# PeripheralMain.net
KiCad netlist of a schematic drawn in Altium Designer
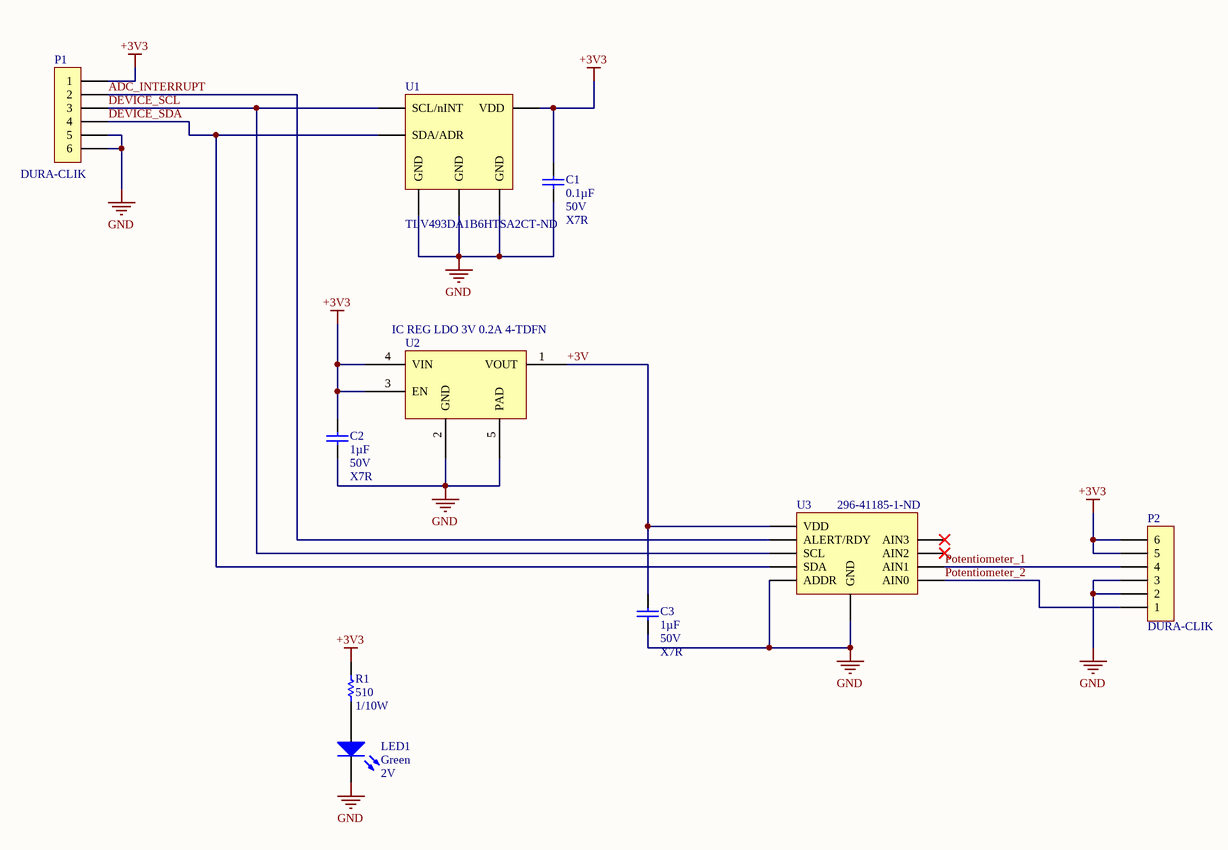
[diagram p0: PeripheralMain.SchDoc]

(export (version "E")
  (design (tool "Eeschema 10.0.6"))
  (components
    (comp (ref "C1")
      (value "CAP CER 0.1UF 50V 10% X7R 0603")
      (footprint "CAP, 0603")
      (description "0.10µF ±10% 50V Ceramic Capacitor X7R 0603 (1608 Metric)")
      (fields
        (field (name "TOLERANCE") "±10%")
        (field (name "CAPACITANCE") "0.1µF")
        (field (name "VOLTAGE") "50V")
        (field (name "TEMPERATURE COEFFICIENT") "X7R")
      )
      (libsource (lib "Schematic Diagrams") (part "CAP CER 0.1UF 50V 10% X7R 0603"))
    )
    (comp (ref "C2")
      (value "CAP CER 1UF 50V 10% X7R 0603")
      (footprint "CAP, 0603")
      (description "1µF ±10% 50V Ceramic Capacitor X7R 0603 (1608 Metric)")
      (fields
        (field (name "TOLERANCE") "±10%")
        (field (name "CAPACITANCE") "1µF")
        (field (name "VOLTAGE") "50V")
        (field (name "TEMPERATURE COEFFICIENT") "X7R")
      )
      (libsource (lib "Schematic Diagrams") (part "CAP CER 1UF 50V 10% X7R 0603"))
    )
    (comp (ref "C3")
      (value "CAP CER 1UF 50V 10% X7R 0603")
      (footprint "CAP, 0603")
      (description "1µF ±10% 50V Ceramic Capacitor X7R 0603 (1608 Metric)")
      (fields
        (field (name "TOLERANCE") "±10%")
        (field (name "CAPACITANCE") "1µF")
        (field (name "VOLTAGE") "50V")
        (field (name "TEMPERATURE COEFFICIENT") "X7R")
      )
      (libsource (lib "Schematic Diagrams") (part "CAP CER 1UF 50V 10% X7R 0603"))
    )
    (comp (ref "LED1")
      (value "LED GREEN CLEAR 2V 0603")
      (footprint "LED_0603")
      (description "Green 572nm LED Indication - Discrete 2V 0603 (1608 Metric)")
      (fields
        (field (name "MANUFACTURER") "Wurth Electronics Inc.")
        (field (name "MANUFACTURER PART NUMBER") "150060VS75000")
        (field (name "COLOR") "Green")
        (field (name "VOLTAGE - FORWARD (VF) (TYP)") "2V")
      )
      (libsource (lib "Schematic Diagrams") (part "LED GREEN CLEAR 2V 0603"))
    )
    (comp (ref "P1")
      (value "DURA-CLIK")
      (footprint "CONN, 6POS DURA-CLIK VERT")
      (description "6 Positions Header, Shrouded Connector 0.079\" (2.00mm) Surface Mount, Vertical Tin")
      (fields (field (name "MANUFACTURER") "Molex") (field (name "MANUFACTURER PART NUMBER") "5600200820"))
      (libsource (lib "") (part "CONN 6POS DURA-CLIK 0.079{dblquote}_1"))
    )
    (comp (ref "P2")
      (value "DURA-CLIK")
      (footprint "CONN, 6POS DURA-CLIK VERT")
      (description "6 Positions Header, Shrouded Connector 0.079\" (2.00mm) Surface Mount, Vertical Tin")
      (fields (field (name "MANUFACTURER") "Molex") (field (name "MANUFACTURER PART NUMBER") "5600200820"))
      (libsource (lib "Schematic Diagrams") (part "CONN 6POS DURA-CLIK 0.079{dblquote}"))
    )
    (comp (ref "R1")
      (value "RES 510 OHM 5% 1/10W 0603")
      (footprint "RES, 0603")
      (description "RES SMD 510 OHM 5% 1/10W 0603")
      (fields
        (field (name "TOLERANCE") "±5%")
        (field (name "RESISTANCE") "510")
        (field (name "POWER") "1/10W")
      )
      (libsource (lib "Schematic Diagrams") (part "RES 510 OHM 5% 1/10W 0603"))
    )
    (comp (ref "U1")
      (value "HALL EFFECT")
      (footprint "IC TLV496D MAG SENSOR TSOP-6")
      (description "Hall Effect Sensor Linear, Rotary Position External Magnet Not Included SMD (SMT) Tab")
      (fields
        (field (name "MANUFACTURER") "Infineon Technologies")
        (field (name "MANUFACTURER PART NUMBER") "TLV493DA1B6HTSA2")
        (field (name "SUPPLIER PART NUMBER 1") "TLV493DA1B6HTSA2CT-ND")
      )
      (libsource (lib "Schematic Diagrams") (part "IC SENSOR HALL I2C TSOP-6"))
    )
    (comp (ref "U2")
      (value "IC REG LDO 3V 0.2A 4-TDFN")
      (footprint "IC REG LDO 3V 0.2A 4-TDFN")
      (fields
        (field (name "MANUFACTURER") "Microchip Technology")
        (field (name "MANUFACTURER PART NUMBER") "MIC94310-PYMT-TR")
      )
      (libsource (lib "Schematic Diagrams") (part "IC REG LDO 3V 0.2A 4-TDFN"))
    )
    (comp (ref "U3")
      (value "Quad ADC")
      (footprint "IC ADC VSSOP10")
      (description "12 Bit Analog to Digital Converter 4 Input 1 Sigma-Delta 10-VSSOP")
      (fields
        (field (name "MANUFACTURER") "Texas Instruments")
        (field (name "MANUFACTURER PART NUMBER") "ADS1015IDGSR")
        (field (name "SUPPLIER PART NUMBER 1") "296-41185-1-ND")
      )
      (libsource (lib "Schematic Diagrams") (part "IC ADC 12-BIT VSSOP-10"))
    )
  )
  (nets
    (net (code "1") (name "+3V3") (class "Default")
      (node (ref "C1") (pin "1") (pinfunction "1_1") (pintype "passive"))
      (node (ref "C2") (pin "1") (pinfunction "1_1") (pintype "passive"))
      (node (ref "P1") (pin "1") (pinfunction "1_1") (pintype "passive"))
      (node (ref "P2") (pin "5") (pinfunction "5_5") (pintype "passive"))
      (node (ref "P2") (pin "6") (pinfunction "6_6") (pintype "passive"))
      (node (ref "R1") (pin "1") (pinfunction "1_1") (pintype "passive"))
      (node (ref "U1") (pin "4") (pinfunction "VDD_4") (pintype "passive"))
      (node (ref "U2") (pin "3") (pinfunction "EN_3") (pintype "passive"))
      (node (ref "U2") (pin "4") (pinfunction "VIN_4") (pintype "passive"))
    )
    (net (code "2") (name "/+3V") (class "Default")
      (node (ref "C3") (pin "1") (pinfunction "1_1") (pintype "passive"))
      (node (ref "U2") (pin "1") (pinfunction "VOUT_1") (pintype "passive"))
      (node (ref "U3") (pin "8") (pinfunction "VDD_8") (pintype "passive"))
    )
    (net (code "3") (name "/ADC_INTERRUPT") (class "Default")
      (node (ref "P1") (pin "2") (pinfunction "2_2") (pintype "passive"))
      (node (ref "U3") (pin "2") (pinfunction "ALERT/RDY_2") (pintype "passive"))
    )
    (net (code "4") (name "/DEVICE_SCL") (class "Default")
      (node (ref "P1") (pin "3") (pinfunction "3_3") (pintype "passive"))
      (node (ref "U1") (pin "1") (pinfunction "SCL/nINT_1") (pintype "passive"))
      (node (ref "U3") (pin "10") (pinfunction "SCL_10") (pintype "passive"))
    )
    (net (code "5") (name "/DEVICE_SDA") (class "Default")
      (node (ref "P1") (pin "4") (pinfunction "4_4") (pintype "passive"))
      (node (ref "U1") (pin "6") (pinfunction "SDA/ADR_6") (pintype "passive"))
      (node (ref "U3") (pin "9") (pinfunction "SDA_9") (pintype "passive"))
    )
    (net (code "6") (name "/Potentiometer_1") (class "Default")
      (node (ref "P2") (pin "4") (pinfunction "4_4") (pintype "passive"))
      (node (ref "U3") (pin "5") (pinfunction "AIN1_5") (pintype "passive"))
    )
    (net (code "7") (name "/Potentiometer_2") (class "Default")
      (node (ref "P2") (pin "1") (pinfunction "1_1") (pintype "passive"))
      (node (ref "U3") (pin "4") (pinfunction "AIN0_4") (pintype "passive"))
    )
    (net (code "8") (name "GND") (class "Default")
      (node (ref "C1") (pin "2") (pinfunction "2_2") (pintype "passive"))
      (node (ref "C2") (pin "2") (pinfunction "2_2") (pintype "passive"))
      (node (ref "C3") (pin "2") (pinfunction "2_2") (pintype "passive"))
      (node (ref "LED1") (pin "2") (pinfunction "K_2") (pintype "passive"))
      (node (ref "P1") (pin "5") (pinfunction "5_5") (pintype "passive"))
      (node (ref "P1") (pin "6") (pinfunction "6_6") (pintype "passive"))
      (node (ref "P2") (pin "2") (pinfunction "2_2") (pintype "passive"))
      (node (ref "P2") (pin "3") (pinfunction "3_3") (pintype "passive"))
      (node (ref "U1") (pin "2") (pinfunction "GND_2") (pintype "passive"))
      (node (ref "U1") (pin "3") (pinfunction "GND_3") (pintype "passive"))
      (node (ref "U1") (pin "5") (pinfunction "GND_5") (pintype "passive"))
      (node (ref "U2") (pin "2") (pinfunction "GND_2") (pintype "passive"))
      (node (ref "U2") (pin "5") (pinfunction "PAD_5") (pintype "passive"))
      (node (ref "U3") (pin "1") (pinfunction "ADDR_1") (pintype "passive"))
      (node (ref "U3") (pin "3") (pinfunction "GND_3") (pintype "passive"))
    )
    (net (code "9") (name "Net-(LED1-A)") (class "Default")
      (node (ref "LED1") (pin "1") (pinfunction "A_1") (pintype "passive"))
      (node (ref "R1") (pin "2") (pinfunction "2_2") (pintype "passive"))
    )
    (net (code "10") (name "unconnected-(U3-AIN2-Pad6)") (class "Default")
      (node (ref "U3") (pin "6") (pinfunction "AIN2_6") (pintype "passive+no_connect"))
    )
    (net (code "11") (name "unconnected-(U3-AIN3-Pad7)") (class "Default")
      (node (ref "U3") (pin "7") (pinfunction "AIN3_7") (pintype "passive+no_connect"))
    )
  )
)
